# TIDA-010933-DCDC-ControlCard.net
KiCad netlist of a schematic drawn in Altium Designer
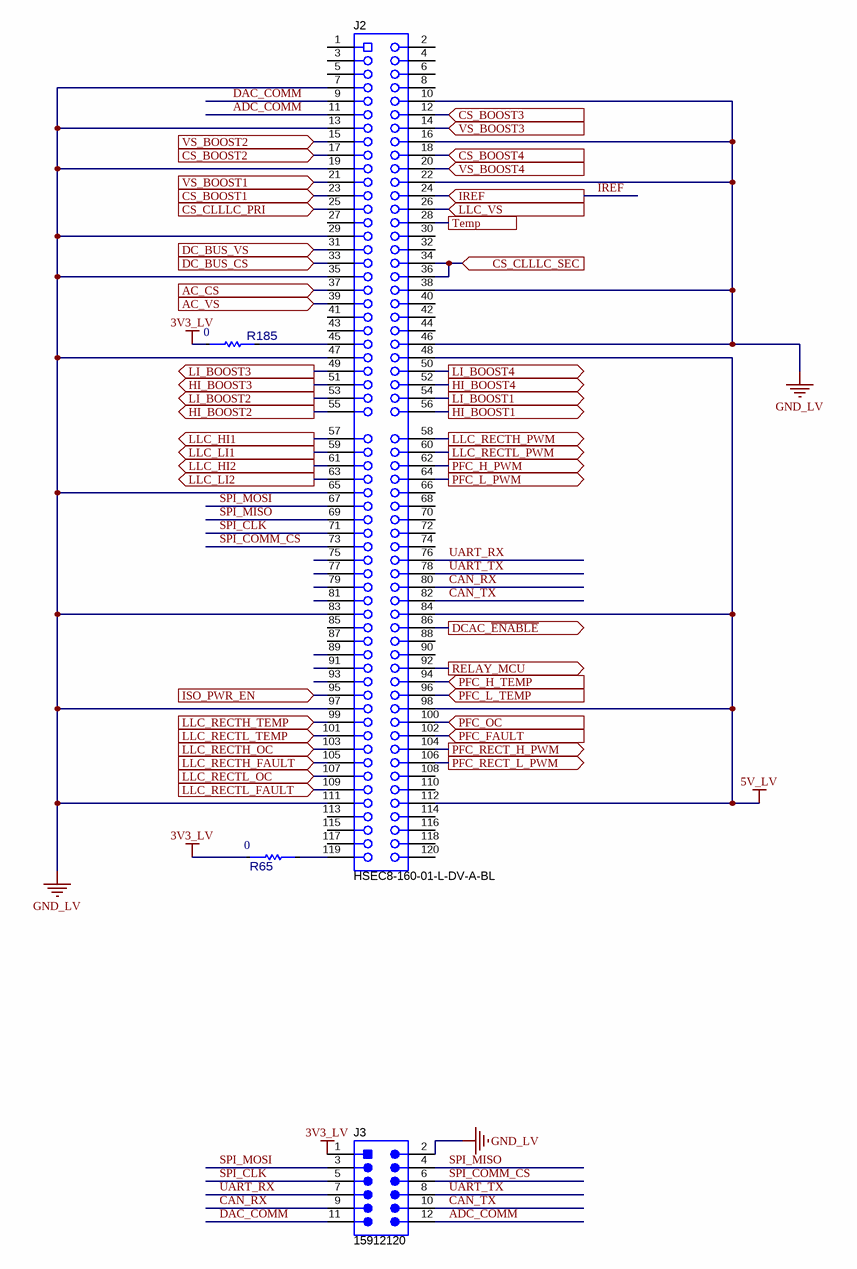
[diagram p0: TIDA-010933-DCDC-ControlCard.SchDoc]

(export (version "E")
  (design (tool "Eeschema 10.0.6"))
  (components
    (comp (ref "J2")
      (value "HSEC8-160-01-L-DV-A-BL")
      (footprint "controlCARD-120HSEC")
      (description "C2000 controlCARD-120HSEC connector, SMT")
      (fields (field (name "MANUFACTURER") "Samtec"))
      (libsource (lib "Altium Vault - TI") (part "controlCARD-120HSEC"))
    )
    (comp (ref "J3")
      (value "15912120")
      (footprint "MOLEX_0015912120")
      (description "Header, 100mil, 6x2, SMT")
      (fields (field (name "MANUFACTURER") "Molex"))
      (libsource (lib "Altium Vault - TI") (part "Header_6x2"))
    )
    (comp (ref "R65")
      (value "0")
      (footprint "FP-RC0402JR-070RP_0402-MFG")
      (description "Res Jumper Thick Film 0402 0 Ohm 5% 1/16W Molded SMD Paper T/R")
      (fields (field (name "MOUSER PART NUMBER") "603-RC0402JR-070RP") (field (name "MANUFACTURER") "Yageo"))
      (libsource (lib "Altium Vault - TI") (part "SYM-RC0402JR-070RP"))
    )
    (comp (ref "R185")
      (value "0")
      (footprint "FP-RC0402JR-070RP_0402-MFG")
      (description "Res Jumper Thick Film 0402 0 Ohm 5% 1/16W Molded SMD Paper T/R")
      (fields (field (name "MOUSER PART NUMBER") "603-RC0402JR-070RP") (field (name "MANUFACTURER") "Yageo"))
      (libsource (lib "Altium Vault - TI") (part "SYM-RC0402JR-070RP"))
    )
  )
  (nets
    (net (code "1") (name "/AC_CS") (class "Default")
      (node (ref "J2") (pin "37") (pinfunction "37_37") (pintype "passive"))
    )
    (net (code "2") (name "/AC_VS") (class "Default")
      (node (ref "J2") (pin "39") (pinfunction "39_39") (pintype "passive"))
    )
    (net (code "3") (name "/ADC_COMM") (class "Default")
      (node (ref "J2") (pin "11") (pinfunction "11_11") (pintype "passive"))
      (node (ref "J3") (pin "12") (pinfunction "12_12") (pintype "passive"))
    )
    (net (code "4") (name "/CAN_RX") (class "Default")
      (node (ref "J2") (pin "80") (pinfunction "80_80") (pintype "passive"))
      (node (ref "J3") (pin "9") (pinfunction "9_9") (pintype "passive"))
    )
    (net (code "5") (name "/CAN_TX") (class "Default")
      (node (ref "J2") (pin "82") (pinfunction "82_82") (pintype "passive"))
      (node (ref "J3") (pin "10") (pinfunction "10_10") (pintype "passive"))
    )
    (net (code "6") (name "/CS_BOOST1") (class "Default")
      (node (ref "J2") (pin "23") (pinfunction "23_23") (pintype "passive"))
    )
    (net (code "7") (name "/CS_BOOST2") (class "Default")
      (node (ref "J2") (pin "17") (pinfunction "17_17") (pintype "passive"))
    )
    (net (code "8") (name "/CS_BOOST3") (class "Default")
      (node (ref "J2") (pin "12") (pinfunction "12_12") (pintype "passive"))
    )
    (net (code "9") (name "/CS_BOOST4") (class "Default")
      (node (ref "J2") (pin "18") (pinfunction "18_18") (pintype "passive"))
    )
    (net (code "10") (name "/CS_CLLLC_PRI") (class "Default")
      (node (ref "J2") (pin "25") (pinfunction "25_25") (pintype "passive"))
    )
    (net (code "11") (name "/CS_CLLLC_SEC") (class "Default")
      (node (ref "J2") (pin "34") (pinfunction "34_34") (pintype "passive"))
      (node (ref "J2") (pin "36") (pinfunction "36_36") (pintype "passive"))
    )
    (net (code "12") (name "/DAC_COMM") (class "Default")
      (node (ref "J2") (pin "9") (pinfunction "9_9") (pintype "passive"))
      (node (ref "J3") (pin "11") (pinfunction "11_11") (pintype "passive"))
    )
    (net (code "13") (name "/DCAC_~{ENABLE}") (class "Default")
      (node (ref "J2") (pin "86") (pinfunction "86_86") (pintype "passive"))
    )
    (net (code "14") (name "/DC_BUS_CS") (class "Default")
      (node (ref "J2") (pin "33") (pinfunction "33_33") (pintype "passive"))
    )
    (net (code "15") (name "/DC_BUS_VS") (class "Default")
      (node (ref "J2") (pin "31") (pinfunction "31_31") (pintype "passive"))
    )
    (net (code "16") (name "/HI_BOOST1") (class "Default")
      (node (ref "J2") (pin "56") (pinfunction "56_56") (pintype "passive"))
    )
    (net (code "17") (name "/HI_BOOST2") (class "Default")
      (node (ref "J2") (pin "55") (pinfunction "55_55") (pintype "passive"))
    )
    (net (code "18") (name "/HI_BOOST3") (class "Default")
      (node (ref "J2") (pin "51") (pinfunction "51_51") (pintype "passive"))
    )
    (net (code "19") (name "/HI_BOOST4") (class "Default")
      (node (ref "J2") (pin "52") (pinfunction "52_52") (pintype "passive"))
    )
    (net (code "20") (name "/IREF") (class "Default")
      (node (ref "J2") (pin "24") (pinfunction "24_24") (pintype "passive"))
    )
    (net (code "21") (name "/ISO_PWR_EN") (class "Default")
      (node (ref "J2") (pin "95") (pinfunction "95_95") (pintype "passive"))
    )
    (net (code "22") (name "/LI_BOOST1") (class "Default")
      (node (ref "J2") (pin "54") (pinfunction "54_54") (pintype "passive"))
    )
    (net (code "23") (name "/LI_BOOST2") (class "Default")
      (node (ref "J2") (pin "53") (pinfunction "53_53") (pintype "passive"))
    )
    (net (code "24") (name "/LI_BOOST3") (class "Default")
      (node (ref "J2") (pin "49") (pinfunction "49_49") (pintype "passive"))
    )
    (net (code "25") (name "/LI_BOOST4") (class "Default")
      (node (ref "J2") (pin "50") (pinfunction "50_50") (pintype "passive"))
    )
    (net (code "26") (name "/LLC_HI1") (class "Default")
      (node (ref "J2") (pin "57") (pinfunction "57_57") (pintype "passive"))
    )
    (net (code "27") (name "/LLC_HI2") (class "Default")
      (node (ref "J2") (pin "61") (pinfunction "61_61") (pintype "passive"))
    )
    (net (code "28") (name "/LLC_LI1") (class "Default")
      (node (ref "J2") (pin "59") (pinfunction "59_59") (pintype "passive"))
    )
    (net (code "29") (name "/LLC_LI2") (class "Default")
      (node (ref "J2") (pin "63") (pinfunction "63_63") (pintype "passive"))
    )
    (net (code "30") (name "/LLC_RECTH_FAULT") (class "Default")
      (node (ref "J2") (pin "105") (pinfunction "105_105") (pintype "passive"))
    )
    (net (code "31") (name "/LLC_RECTH_OC") (class "Default")
      (node (ref "J2") (pin "103") (pinfunction "103_103") (pintype "passive"))
    )
    (net (code "32") (name "/LLC_RECTH_PWM") (class "Default")
      (node (ref "J2") (pin "58") (pinfunction "58_58") (pintype "passive"))
    )
    (net (code "33") (name "/LLC_RECTH_TEMP") (class "Default")
      (node (ref "J2") (pin "99") (pinfunction "99_99") (pintype "passive"))
    )
    (net (code "34") (name "/LLC_RECTL_FAULT") (class "Default")
      (node (ref "J2") (pin "109") (pinfunction "109_109") (pintype "passive"))
    )
    (net (code "35") (name "/LLC_RECTL_OC") (class "Default")
      (node (ref "J2") (pin "107") (pinfunction "107_107") (pintype "passive"))
    )
    (net (code "36") (name "/LLC_RECTL_PWM") (class "Default")
      (node (ref "J2") (pin "60") (pinfunction "60_60") (pintype "passive"))
    )
    (net (code "37") (name "/LLC_RECTL_TEMP") (class "Default")
      (node (ref "J2") (pin "101") (pinfunction "101_101") (pintype "passive"))
    )
    (net (code "38") (name "/LLC_VS") (class "Default")
      (node (ref "J2") (pin "26") (pinfunction "26_26") (pintype "passive"))
    )
    (net (code "39") (name "/PFC_FAULT") (class "Default")
      (node (ref "J2") (pin "102") (pinfunction "102_102") (pintype "passive"))
    )
    (net (code "40") (name "/PFC_H_PWM") (class "Default")
      (node (ref "J2") (pin "62") (pinfunction "62_62") (pintype "passive"))
    )
    (net (code "41") (name "/PFC_H_TEMP") (class "Default")
      (node (ref "J2") (pin "94") (pinfunction "94_94") (pintype "passive"))
    )
    (net (code "42") (name "/PFC_L_PWM") (class "Default")
      (node (ref "J2") (pin "64") (pinfunction "64_64") (pintype "passive"))
    )
    (net (code "43") (name "/PFC_L_TEMP") (class "Default")
      (node (ref "J2") (pin "96") (pinfunction "96_96") (pintype "passive"))
    )
    (net (code "44") (name "/PFC_OC") (class "Default")
      (node (ref "J2") (pin "100") (pinfunction "100_100") (pintype "passive"))
    )
    (net (code "45") (name "/PFC_RECT_H_PWM") (class "Default")
      (node (ref "J2") (pin "104") (pinfunction "104_104") (pintype "passive"))
    )
    (net (code "46") (name "/PFC_RECT_L_PWM") (class "Default")
      (node (ref "J2") (pin "106") (pinfunction "106_106") (pintype "passive"))
    )
    (net (code "47") (name "/RELAY_MCU") (class "Default")
      (node (ref "J2") (pin "92") (pinfunction "92_92") (pintype "passive"))
    )
    (net (code "48") (name "/SPI_CLK") (class "Default")
      (node (ref "J2") (pin "71") (pinfunction "71_71") (pintype "passive"))
      (node (ref "J3") (pin "5") (pinfunction "5_5") (pintype "passive"))
    )
    (net (code "49") (name "/SPI_COMM_CS") (class "Default")
      (node (ref "J2") (pin "73") (pinfunction "73_73") (pintype "passive"))
      (node (ref "J3") (pin "6") (pinfunction "6_6") (pintype "passive"))
    )
    (net (code "50") (name "/SPI_MISO") (class "Default")
      (node (ref "J2") (pin "69") (pinfunction "69_69") (pintype "passive"))
      (node (ref "J3") (pin "4") (pinfunction "4_4") (pintype "passive"))
    )
    (net (code "51") (name "/SPI_MOSI") (class "Default")
      (node (ref "J2") (pin "67") (pinfunction "67_67") (pintype "passive"))
      (node (ref "J3") (pin "3") (pinfunction "3_3") (pintype "passive"))
    )
    (net (code "52") (name "/Temp") (class "Default")
      (node (ref "J2") (pin "28") (pinfunction "28_28") (pintype "passive"))
    )
    (net (code "53") (name "/UART_RX") (class "Default")
      (node (ref "J2") (pin "76") (pinfunction "76_76") (pintype "passive"))
      (node (ref "J3") (pin "7") (pinfunction "7_7") (pintype "passive"))
    )
    (net (code "54") (name "/UART_TX") (class "Default")
      (node (ref "J2") (pin "78") (pinfunction "78_78") (pintype "passive"))
      (node (ref "J3") (pin "8") (pinfunction "8_8") (pintype "passive"))
    )
    (net (code "55") (name "/VS_BOOST1") (class "Default")
      (node (ref "J2") (pin "21") (pinfunction "21_21") (pintype "passive"))
    )
    (net (code "56") (name "/VS_BOOST2") (class "Default")
      (node (ref "J2") (pin "15") (pinfunction "15_15") (pintype "passive"))
    )
    (net (code "57") (name "/VS_BOOST3") (class "Default")
      (node (ref "J2") (pin "14") (pinfunction "14_14") (pintype "passive"))
    )
    (net (code "58") (name "/VS_BOOST4") (class "Default")
      (node (ref "J2") (pin "20") (pinfunction "20_20") (pintype "passive"))
    )
    (net (code "59") (name "3V3_LV") (class "Default")
      (node (ref "J3") (pin "1") (pinfunction "1_1") (pintype "passive"))
      (node (ref "R185") (pin "1") (pinfunction "1_1") (pintype "passive"))
      (node (ref "R65") (pin "1") (pinfunction "1_1") (pintype "passive"))
    )
    (net (code "60") (name "5V_LV") (class "Default")
      (node (ref "J2") (pin "112") (pinfunction "112_112") (pintype "passive"))
      (node (ref "J2") (pin "48") (pinfunction "48_48") (pintype "passive"))
      (node (ref "J2") (pin "84") (pinfunction "84_84") (pintype "passive"))
      (node (ref "J2") (pin "98") (pinfunction "98_98") (pintype "passive"))
    )
    (net (code "61") (name "GND_LV") (class "Default")
      (node (ref "J2") (pin "10") (pinfunction "10_10") (pintype "passive"))
      (node (ref "J2") (pin "111") (pinfunction "111_111") (pintype "passive"))
      (node (ref "J2") (pin "13") (pinfunction "13_13") (pintype "passive"))
      (node (ref "J2") (pin "16") (pinfunction "16_16") (pintype "passive"))
      (node (ref "J2") (pin "19") (pinfunction "19_19") (pintype "passive"))
      (node (ref "J2") (pin "22") (pinfunction "22_22") (pintype "passive"))
      (node (ref "J2") (pin "29") (pinfunction "29_29") (pintype "passive"))
      (node (ref "J2") (pin "35") (pinfunction "35_35") (pintype "passive"))
      (node (ref "J2") (pin "38") (pinfunction "38_38") (pintype "passive"))
      (node (ref "J2") (pin "46") (pinfunction "46_46") (pintype "passive"))
      (node (ref "J2") (pin "47") (pinfunction "47_47") (pintype "passive"))
      (node (ref "J2") (pin "65") (pinfunction "65_65") (pintype "passive"))
      (node (ref "J2") (pin "7") (pinfunction "7_7") (pintype "passive"))
      (node (ref "J2") (pin "83") (pinfunction "83_83") (pintype "passive"))
      (node (ref "J2") (pin "97") (pinfunction "97_97") (pintype "passive"))
      (node (ref "J3") (pin "2") (pinfunction "2_2") (pintype "passive"))
    )
    (net (code "62") (name "Net-(J2-Pad45)") (class "Default")
      (node (ref "J2") (pin "45") (pinfunction "45_45") (pintype "passive"))
      (node (ref "R185") (pin "2") (pinfunction "2_2") (pintype "passive"))
    )
    (net (code "63") (name "Net-(J2-Pad119)") (class "Default")
      (node (ref "J2") (pin "119") (pinfunction "119_119") (pintype "passive"))
      (node (ref "R65") (pin "2") (pinfunction "2_2") (pintype "passive"))
    )
    (net (code "64") (name "unconnected-(J2-Pad1)") (class "Default")
      (node (ref "J2") (pin "1") (pinfunction "1_1") (pintype "passive"))
    )
    (net (code "65") (name "unconnected-(J2-Pad2)") (class "Default")
      (node (ref "J2") (pin "2") (pinfunction "2_2") (pintype "passive"))
    )
    (net (code "66") (name "unconnected-(J2-Pad3)") (class "Default")
      (node (ref "J2") (pin "3") (pinfunction "3_3") (pintype "passive"))
    )
    (net (code "67") (name "unconnected-(J2-Pad4)") (class "Default")
      (node (ref "J2") (pin "4") (pinfunction "4_4") (pintype "passive"))
    )
    (net (code "68") (name "unconnected-(J2-Pad5)") (class "Default")
      (node (ref "J2") (pin "5") (pinfunction "5_5") (pintype "passive"))
    )
    (net (code "69") (name "unconnected-(J2-Pad6)") (class "Default")
      (node (ref "J2") (pin "6") (pinfunction "6_6") (pintype "passive"))
    )
    (net (code "70") (name "unconnected-(J2-Pad8)") (class "Default")
      (node (ref "J2") (pin "8") (pinfunction "8_8") (pintype "passive"))
    )
    (net (code "71") (name "unconnected-(J2-Pad27)") (class "Default")
      (node (ref "J2") (pin "27") (pinfunction "27_27") (pintype "passive"))
    )
    (net (code "72") (name "unconnected-(J2-Pad30)") (class "Default")
      (node (ref "J2") (pin "30") (pinfunction "30_30") (pintype "passive"))
    )
    (net (code "73") (name "unconnected-(J2-Pad32)") (class "Default")
      (node (ref "J2") (pin "32") (pinfunction "32_32") (pintype "passive"))
    )
    (net (code "74") (name "unconnected-(J2-Pad40)") (class "Default")
      (node (ref "J2") (pin "40") (pinfunction "40_40") (pintype "passive"))
    )
    (net (code "75") (name "unconnected-(J2-Pad41)") (class "Default")
      (node (ref "J2") (pin "41") (pinfunction "41_41") (pintype "passive"))
    )
    (net (code "76") (name "unconnected-(J2-Pad42)") (class "Default")
      (node (ref "J2") (pin "42") (pinfunction "42_42") (pintype "passive"))
    )
    (net (code "77") (name "unconnected-(J2-Pad43)") (class "Default")
      (node (ref "J2") (pin "43") (pinfunction "43_43") (pintype "passive"))
    )
    (net (code "78") (name "unconnected-(J2-Pad44)") (class "Default")
      (node (ref "J2") (pin "44") (pinfunction "44_44") (pintype "passive"))
    )
    (net (code "79") (name "unconnected-(J2-Pad66)") (class "Default")
      (node (ref "J2") (pin "66") (pinfunction "66_66") (pintype "passive"))
    )
    (net (code "80") (name "unconnected-(J2-Pad68)") (class "Default")
      (node (ref "J2") (pin "68") (pinfunction "68_68") (pintype "passive"))
    )
    (net (code "81") (name "unconnected-(J2-Pad70)") (class "Default")
      (node (ref "J2") (pin "70") (pinfunction "70_70") (pintype "passive"))
    )
    (net (code "82") (name "unconnected-(J2-Pad72)") (class "Default")
      (node (ref "J2") (pin "72") (pinfunction "72_72") (pintype "passive"))
    )
    (net (code "83") (name "unconnected-(J2-Pad74)") (class "Default")
      (node (ref "J2") (pin "74") (pinfunction "74_74") (pintype "passive"))
    )
    (net (code "84") (name "unconnected-(J2-Pad75)") (class "Default")
      (node (ref "J2") (pin "75") (pinfunction "75_75") (pintype "passive"))
    )
    (net (code "85") (name "unconnected-(J2-Pad77)") (class "Default")
      (node (ref "J2") (pin "77") (pinfunction "77_77") (pintype "passive"))
    )
    (net (code "86") (name "unconnected-(J2-Pad79)") (class "Default")
      (node (ref "J2") (pin "79") (pinfunction "79_79") (pintype "passive"))
    )
    (net (code "87") (name "unconnected-(J2-Pad81)") (class "Default")
      (node (ref "J2") (pin "81") (pinfunction "81_81") (pintype "passive"))
    )
    (net (code "88") (name "unconnected-(J2-Pad85)") (class "Default")
      (node (ref "J2") (pin "85") (pinfunction "85_85") (pintype "passive"))
    )
    (net (code "89") (name "unconnected-(J2-Pad87)") (class "Default")
      (node (ref "J2") (pin "87") (pinfunction "87_87") (pintype "passive"))
    )
    (net (code "90") (name "unconnected-(J2-Pad88)") (class "Default")
      (node (ref "J2") (pin "88") (pinfunction "88_88") (pintype "passive"))
    )
    (net (code "91") (name "unconnected-(J2-Pad89)") (class "Default")
      (node (ref "J2") (pin "89") (pinfunction "89_89") (pintype "passive"))
    )
    (net (code "92") (name "unconnected-(J2-Pad90)") (class "Default")
      (node (ref "J2") (pin "90") (pinfunction "90_90") (pintype "passive"))
    )
    (net (code "93") (name "unconnected-(J2-Pad91)") (class "Default")
      (node (ref "J2") (pin "91") (pinfunction "91_91") (pintype "passive"))
    )
    (net (code "94") (name "unconnected-(J2-Pad93)") (class "Default")
      (node (ref "J2") (pin "93") (pinfunction "93_93") (pintype "passive"))
    )
    (net (code "95") (name "unconnected-(J2-Pad108)") (class "Default")
      (node (ref "J2") (pin "108") (pinfunction "108_108") (pintype "passive"))
    )
    (net (code "96") (name "unconnected-(J2-Pad110)") (class "Default")
      (node (ref "J2") (pin "110") (pinfunction "110_110") (pintype "passive"))
    )
    (net (code "97") (name "unconnected-(J2-Pad113)") (class "Default")
      (node (ref "J2") (pin "113") (pinfunction "113_113") (pintype "passive"))
    )
    (net (code "98") (name "unconnected-(J2-Pad114)") (class "Default")
      (node (ref "J2") (pin "114") (pinfunction "114_114") (pintype "passive"))
    )
    (net (code "99") (name "unconnected-(J2-Pad115)") (class "Default")
      (node (ref "J2") (pin "115") (pinfunction "115_115") (pintype "passive"))
    )
    (net (code "100") (name "unconnected-(J2-Pad116)") (class "Default")
      (node (ref "J2") (pin "116") (pinfunction "116_116") (pintype "passive"))
    )
    (net (code "101") (name "unconnected-(J2-Pad117)") (class "Default")
      (node (ref "J2") (pin "117") (pinfunction "117_117") (pintype "passive"))
    )
    (net (code "102") (name "unconnected-(J2-Pad118)") (class "Default")
      (node (ref "J2") (pin "118") (pinfunction "118_118") (pintype "passive"))
    )
    (net (code "103") (name "unconnected-(J2-Pad120)") (class "Default")
      (node (ref "J2") (pin "120") (pinfunction "120_120") (pintype "passive"))
    )
  )
)
